# encoder.net
KiCad netlist of a schematic drawn in EAGLE
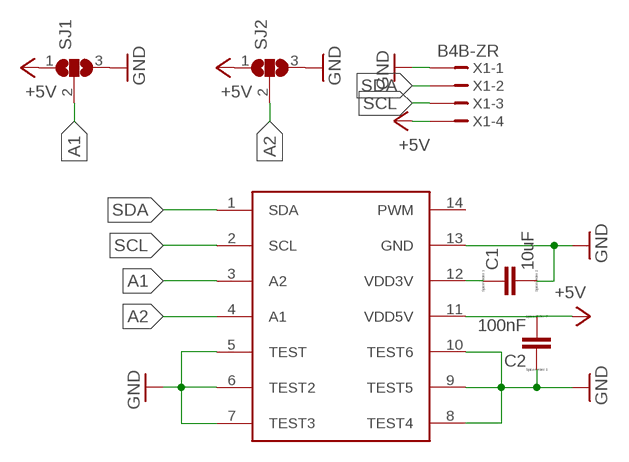
[diagram p0: schematic, sheet 1]

(export (version "E")
  (design (tool "Eeschema 10.0.6"))
  (components
    (comp (ref "C1")
      (value "10uF")
      (footprint "eagle-import:C0805K")
      (libsource (lib "eagle-import") (part "C-EUC0805K"))
    )
    (comp (ref "C2")
      (value "100nF")
      (footprint "eagle-import:C0805K")
      (libsource (lib "eagle-import") (part "C-EUC0805K"))
    )
    (comp (ref "SJ1")
      (value "SJ2W")
      (footprint "eagle-import:SJ_2")
      (libsource (lib "eagle-import") (part "SJ2W"))
    )
    (comp (ref "SJ2")
      (value "SJ2W")
      (footprint "eagle-import:SJ_2")
      (libsource (lib "eagle-import") (part "SJ2W"))
    )
    (comp (ref "U$1")
      (value "AS5048B")
      (footprint "eagle-import:TSSOP14")
      (libsource (lib "eagle-import") (part "AS5048B"))
    )
    (comp (ref "X1")
      (value "B4B-ZR")
      (footprint "eagle-import:B4B-ZR")
      (fields (field (name "MF") "FARNELL") (field (name "MPN") "B4B-ZR(LF)(SN)"))
      (libsource (lib "eagle-import") (part "?4B-ZRB"))
    )
  )
  (nets
    (net (code "1") (name "+5V") (class "Default")
      (node (ref "C2") (pin "2") (pinfunction "2_2") (pintype "passive"))
      (node (ref "SJ1") (pin "1") (pinfunction "1_1") (pintype "passive"))
      (node (ref "SJ2") (pin "1") (pinfunction "1_1") (pintype "passive"))
      (node (ref "U$1") (pin "11") (pinfunction "VDD5V_11") (pintype "bidirectional"))
      (node (ref "X1") (pin "4") (pinfunction "1_4") (pintype "passive"))
    )
    (net (code "2") (name "A1") (class "Default")
      (node (ref "SJ1") (pin "2") (pinfunction "2_2") (pintype "passive"))
      (node (ref "U$1") (pin "3") (pinfunction "A2_3") (pintype "bidirectional"))
    )
    (net (code "3") (name "A2") (class "Default")
      (node (ref "SJ2") (pin "2") (pinfunction "2_2") (pintype "passive"))
      (node (ref "U$1") (pin "4") (pinfunction "A1_4") (pintype "bidirectional"))
    )
    (net (code "4") (name "GND") (class "Default")
      (node (ref "C1") (pin "2") (pinfunction "2_2") (pintype "passive"))
      (node (ref "C2") (pin "1") (pinfunction "1_1") (pintype "passive"))
      (node (ref "SJ1") (pin "3") (pinfunction "3_3") (pintype "passive"))
      (node (ref "SJ2") (pin "3") (pinfunction "3_3") (pintype "passive"))
      (node (ref "U$1") (pin "10") (pinfunction "TEST6_10") (pintype "bidirectional"))
      (node (ref "U$1") (pin "13") (pinfunction "GND_13") (pintype "bidirectional"))
      (node (ref "U$1") (pin "5") (pinfunction "TEST_5") (pintype "bidirectional"))
      (node (ref "U$1") (pin "6") (pinfunction "TEST2_6") (pintype "bidirectional"))
      (node (ref "U$1") (pin "7") (pinfunction "TEST3_7") (pintype "bidirectional"))
      (node (ref "U$1") (pin "8") (pinfunction "TEST4_8") (pintype "bidirectional"))
      (node (ref "U$1") (pin "9") (pinfunction "TEST5_9") (pintype "bidirectional"))
      (node (ref "X1") (pin "1") (pinfunction "1_1") (pintype "passive"))
    )
    (net (code "5") (name "Net-(U$1-VDD3V)") (class "Default")
      (node (ref "C1") (pin "1") (pinfunction "1_1") (pintype "passive"))
      (node (ref "U$1") (pin "12") (pinfunction "VDD3V_12") (pintype "bidirectional"))
    )
    (net (code "6") (name "SCL") (class "Default")
      (node (ref "U$1") (pin "2") (pinfunction "SCL_2") (pintype "bidirectional"))
      (node (ref "X1") (pin "3") (pinfunction "1_3") (pintype "passive"))
    )
    (net (code "7") (name "SDA") (class "Default")
      (node (ref "U$1") (pin "1") (pinfunction "SDA_1") (pintype "bidirectional"))
      (node (ref "X1") (pin "2") (pinfunction "1_2") (pintype "passive"))
    )
    (net (code "8") (name "unconnected-(U$1-PWM-Pad14)") (class "Default")
      (node (ref "U$1") (pin "14") (pinfunction "PWM_14") (pintype "bidirectional"))
    )
  )
)
